# Touch_Menu_Board.net
KiCad netlist of a schematic drawn in EAGLE
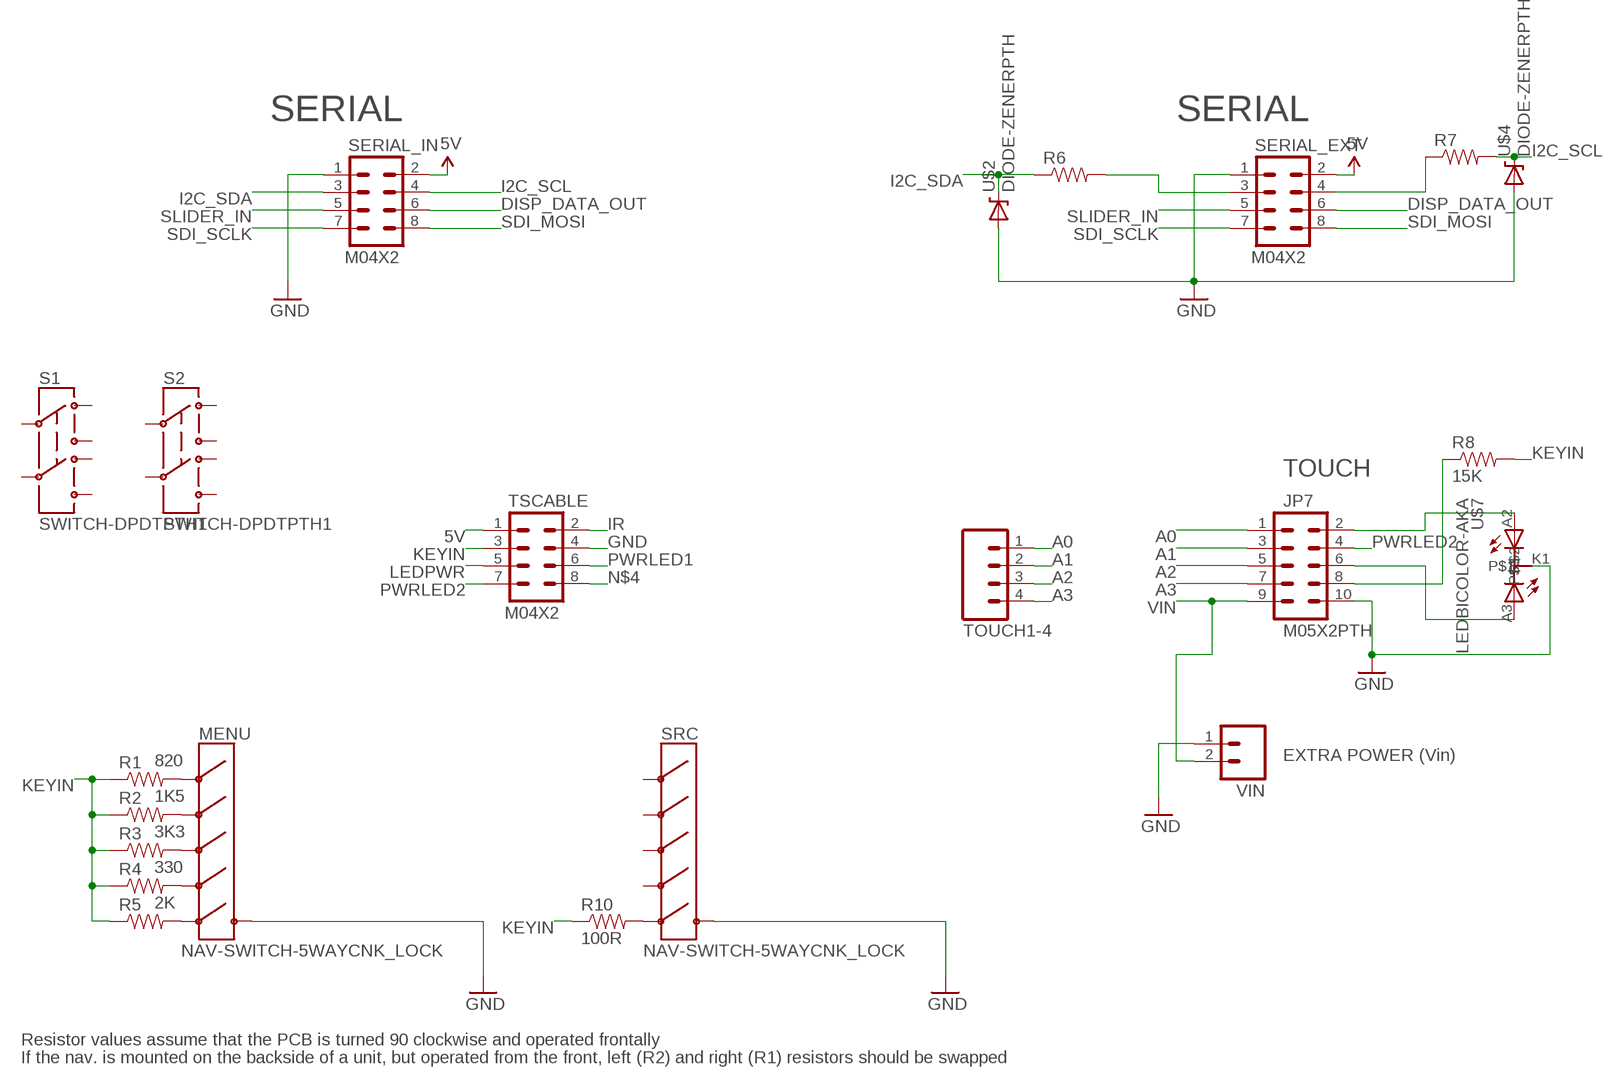
[diagram p0: schematic, sheet 1]

(export (version "E")
  (design (tool "Eeschema 10.0.6"))
  (components
    (comp (ref "JP7")
      (value "M05X2PTH")
      (footprint "eagle-import:AVR_ICSP")
      (libsource (lib "eagle-import") (part "M05X2PTH"))
    )
    (comp (ref "MENU")
      (value "NAV-SWITCH-5WAYCNK_LOCK")
      (footprint "eagle-import:NAV-SWITCH-5WAY")
      (libsource (lib "eagle-import") (part "NAV-SWITCH-5WAYCNK_LOCK"))
    )
    (comp (ref "R1")
      (value "820")
      (footprint "eagle-import:0603-RES")
      (libsource (lib "eagle-import") (part "RESISTOR0603-RES"))
    )
    (comp (ref "R2")
      (value "1K5")
      (footprint "eagle-import:0603-RES")
      (libsource (lib "eagle-import") (part "RESISTOR0603-RES"))
    )
    (comp (ref "R3")
      (value "3K3")
      (footprint "eagle-import:0603-RES")
      (libsource (lib "eagle-import") (part "RESISTOR0603-RES"))
    )
    (comp (ref "R4")
      (value "330")
      (footprint "eagle-import:0603-RES")
      (libsource (lib "eagle-import") (part "RESISTOR0603-RES"))
    )
    (comp (ref "R5")
      (value "2K")
      (footprint "eagle-import:0603-RES")
      (libsource (lib "eagle-import") (part "RESISTOR0603-RES"))
    )
    (comp (ref "R6")
      (value "RESISTORPTH-1/4W")
      (footprint "eagle-import:AXIAL-0.4")
      (libsource (lib "eagle-import") (part "RESISTORPTH-1/4W"))
    )
    (comp (ref "R7")
      (value "RESISTORPTH-1/4W")
      (footprint "eagle-import:AXIAL-0.4")
      (libsource (lib "eagle-import") (part "RESISTORPTH-1/4W"))
    )
    (comp (ref "R8")
      (value "15K")
      (footprint "eagle-import:0603-RES")
      (libsource (lib "eagle-import") (part "RESISTOR0603-RES"))
    )
    (comp (ref "R10")
      (value "100R")
      (footprint "eagle-import:0603-RES")
      (libsource (lib "eagle-import") (part "RESISTOR0603-RES"))
    )
    (comp (ref "S1")
      (value "SWITCH-DPDTPTH1")
      (footprint "eagle-import:TECONNECTIVITY-DPDT")
      (libsource (lib "eagle-import") (part "SWITCH-DPDTPTH1"))
    )
    (comp (ref "S2")
      (value "SWITCH-DPDTPTH1")
      (footprint "eagle-import:TECONNECTIVITY-DPDT")
      (libsource (lib "eagle-import") (part "SWITCH-DPDTPTH1"))
    )
    (comp (ref "SERIAL_EXT")
      (value "M04X2")
      (footprint "eagle-import:2X4")
      (libsource (lib "eagle-import") (part "M04X2"))
    )
    (comp (ref "SERIAL_IN")
      (value "M04X2")
      (footprint "eagle-import:2X4")
      (libsource (lib "eagle-import") (part "M04X2"))
    )
    (comp (ref "SRC")
      (value "NAV-SWITCH-5WAYCNK_LOCK")
      (footprint "eagle-import:NAV-SWITCH-5WAY")
      (libsource (lib "eagle-import") (part "NAV-SWITCH-5WAYCNK_LOCK"))
    )
    (comp (ref "TOUCH1-4")
      (value "M04PTH")
      (footprint "eagle-import:1X04")
      (libsource (lib "eagle-import") (part "M04PTH"))
    )
    (comp (ref "TSCABLE")
      (value "M04X2")
      (footprint "eagle-import:2X4")
      (libsource (lib "eagle-import") (part "M04X2"))
    )
    (comp (ref "U$2")
      (value "DIODE-ZENERPTH")
      (footprint "eagle-import:DIODE-ZENER")
      (libsource (lib "eagle-import") (part "DIODE-ZENERPTH"))
    )
    (comp (ref "U$4")
      (value "DIODE-ZENERPTH")
      (footprint "eagle-import:DIODE-ZENER")
      (libsource (lib "eagle-import") (part "DIODE-ZENERPTH"))
    )
    (comp (ref "U$7")
      (value "LEDBICOLOR-AKA")
      (footprint "eagle-import:LED5MM-BICOLOR")
      (libsource (lib "eagle-import") (part "LEDBICOLOR-AKA"))
    )
    (comp (ref "VIN")
      (value "M02PTH")
      (footprint "eagle-import:1X02")
      (libsource (lib "eagle-import") (part "M02PTH"))
    )
  )
  (nets
    (net (code "1") (name "/A0") (class "Default")
      (node (ref "JP7") (pin "1") (pinfunction "1_1") (pintype "passive"))
      (node (ref "TOUCH1-4") (pin "1") (pinfunction "1_1") (pintype "passive"))
    )
    (net (code "2") (name "/A1") (class "Default")
      (node (ref "JP7") (pin "3") (pinfunction "3_3") (pintype "passive"))
      (node (ref "TOUCH1-4") (pin "2") (pinfunction "2_2") (pintype "passive"))
    )
    (net (code "3") (name "/A2") (class "Default")
      (node (ref "JP7") (pin "5") (pinfunction "5_5") (pintype "passive"))
      (node (ref "TOUCH1-4") (pin "3") (pinfunction "3_3") (pintype "passive"))
    )
    (net (code "4") (name "/A3") (class "Default")
      (node (ref "JP7") (pin "7") (pinfunction "7_7") (pintype "passive"))
      (node (ref "TOUCH1-4") (pin "4") (pinfunction "4_4") (pintype "passive"))
    )
    (net (code "5") (name "/DISP_DATA_OUT") (class "Default")
      (node (ref "SERIAL_EXT") (pin "6") (pinfunction "6_6") (pintype "passive"))
      (node (ref "SERIAL_IN") (pin "6") (pinfunction "6_6") (pintype "passive"))
    )
    (net (code "6") (name "/I2C_SCL") (class "Default")
      (node (ref "R7") (pin "P$2") (pinfunction "2_P$2") (pintype "passive"))
      (node (ref "SERIAL_IN") (pin "4") (pinfunction "4_4") (pintype "passive"))
      (node (ref "U$4") (pin "P$1") (pinfunction "C_P$1") (pintype "passive"))
    )
    (net (code "7") (name "/I2C_SDA") (class "Default")
      (node (ref "R6") (pin "P$1") (pinfunction "1_P$1") (pintype "passive"))
      (node (ref "SERIAL_IN") (pin "3") (pinfunction "3_3") (pintype "passive"))
      (node (ref "U$2") (pin "P$1") (pinfunction "C_P$1") (pintype "passive"))
    )
    (net (code "8") (name "/IR") (class "Default")
      (node (ref "TSCABLE") (pin "2") (pinfunction "2_2") (pintype "passive"))
    )
    (net (code "9") (name "/KEYIN") (class "Default")
      (node (ref "R1") (pin "1") (pinfunction "1_1") (pintype "passive"))
      (node (ref "R10") (pin "1") (pinfunction "1_1") (pintype "passive"))
      (node (ref "R2") (pin "1") (pinfunction "1_1") (pintype "passive"))
      (node (ref "R3") (pin "1") (pinfunction "1_1") (pintype "passive"))
      (node (ref "R4") (pin "1") (pinfunction "1_1") (pintype "passive"))
      (node (ref "R5") (pin "1") (pinfunction "1_1") (pintype "passive"))
      (node (ref "R8") (pin "2") (pinfunction "2_2") (pintype "passive"))
      (node (ref "TSCABLE") (pin "3") (pinfunction "3_3") (pintype "passive"))
    )
    (net (code "10") (name "/LEDPWR") (class "Default")
      (node (ref "TSCABLE") (pin "5") (pinfunction "5_5") (pintype "passive"))
    )
    (net (code "11") (name "/N$4") (class "Default")
      (node (ref "TSCABLE") (pin "8") (pinfunction "8_8") (pintype "passive"))
    )
    (net (code "12") (name "/PWRLED1") (class "Default")
      (node (ref "TSCABLE") (pin "6") (pinfunction "6_6") (pintype "passive"))
    )
    (net (code "13") (name "/PWRLED2") (class "Default")
      (node (ref "JP7") (pin "4") (pinfunction "4_4") (pintype "passive"))
      (node (ref "TSCABLE") (pin "7") (pinfunction "7_7") (pintype "passive"))
    )
    (net (code "14") (name "/SDI_MOSI") (class "Default")
      (node (ref "SERIAL_EXT") (pin "8") (pinfunction "8_8") (pintype "passive"))
      (node (ref "SERIAL_IN") (pin "8") (pinfunction "8_8") (pintype "passive"))
    )
    (net (code "15") (name "/SDI_SCLK") (class "Default")
      (node (ref "SERIAL_EXT") (pin "7") (pinfunction "7_7") (pintype "passive"))
      (node (ref "SERIAL_IN") (pin "7") (pinfunction "7_7") (pintype "passive"))
    )
    (net (code "16") (name "/SLIDER_IN") (class "Default")
      (node (ref "SERIAL_EXT") (pin "5") (pinfunction "5_5") (pintype "passive"))
      (node (ref "SERIAL_IN") (pin "5") (pinfunction "5_5") (pintype "passive"))
    )
    (net (code "17") (name "/VIN") (class "Default")
      (node (ref "JP7") (pin "9") (pinfunction "9_9") (pintype "passive"))
      (node (ref "VIN") (pin "2") (pinfunction "2_2") (pintype "passive"))
    )
    (net (code "18") (name "5V") (class "Default")
      (node (ref "SERIAL_EXT") (pin "2") (pinfunction "2_2") (pintype "passive"))
      (node (ref "SERIAL_IN") (pin "2") (pinfunction "2_2") (pintype "passive"))
      (node (ref "TSCABLE") (pin "1") (pinfunction "1_1") (pintype "passive"))
    )
    (net (code "19") (name "GND") (class "Default")
      (node (ref "JP7") (pin "10") (pinfunction "10_10") (pintype "passive"))
      (node (ref "MENU") (pin "PIN4") (pinfunction "COMMON_PIN4") (pintype "bidirectional"))
      (node (ref "SERIAL_EXT") (pin "1") (pinfunction "1_1") (pintype "passive"))
      (node (ref "SERIAL_IN") (pin "1") (pinfunction "1_1") (pintype "passive"))
      (node (ref "SRC") (pin "PIN4") (pinfunction "COMMON_PIN4") (pintype "bidirectional"))
      (node (ref "TSCABLE") (pin "4") (pinfunction "4_4") (pintype "passive"))
      (node (ref "U$2") (pin "P$2") (pinfunction "A_P$2") (pintype "passive"))
      (node (ref "U$4") (pin "P$2") (pinfunction "A_P$2") (pintype "passive"))
      (node (ref "U$7") (pin "K1") (pinfunction "P$1_K1") (pintype "bidirectional"))
      (node (ref "VIN") (pin "1") (pinfunction "1_1") (pintype "passive"))
    )
    (net (code "20") (name "Net-(JP7-Pad8)") (class "Default")
      (node (ref "JP7") (pin "8") (pinfunction "8_8") (pintype "passive"))
      (node (ref "R8") (pin "1") (pinfunction "1_1") (pintype "passive"))
    )
    (net (code "21") (name "Net-(MENU-DWN)") (class "Default")
      (node (ref "MENU") (pin "PIN3") (pinfunction "DWN_PIN3") (pintype "bidirectional"))
      (node (ref "R2") (pin "2") (pinfunction "2_2") (pintype "passive"))
    )
    (net (code "22") (name "Net-(MENU-LEFT)") (class "Default")
      (node (ref "MENU") (pin "PIN2") (pinfunction "LEFT_PIN2") (pintype "bidirectional"))
      (node (ref "R3") (pin "2") (pinfunction "2_2") (pintype "passive"))
    )
    (net (code "23") (name "Net-(MENU-PUSH)") (class "Default")
      (node (ref "MENU") (pin "PIN6") (pinfunction "PUSH_PIN6") (pintype "bidirectional"))
      (node (ref "R5") (pin "2") (pinfunction "2_2") (pintype "passive"))
    )
    (net (code "24") (name "Net-(MENU-RIGHT)") (class "Default")
      (node (ref "MENU") (pin "PIN5") (pinfunction "RIGHT_PIN5") (pintype "bidirectional"))
      (node (ref "R4") (pin "2") (pinfunction "2_2") (pintype "passive"))
    )
    (net (code "25") (name "Net-(MENU-UP)") (class "Default")
      (node (ref "MENU") (pin "PIN1") (pinfunction "UP_PIN1") (pintype "bidirectional"))
      (node (ref "R1") (pin "2") (pinfunction "2_2") (pintype "passive"))
    )
    (net (code "26") (name "Net-(R6-2)") (class "Default")
      (node (ref "R6") (pin "P$2") (pinfunction "2_P$2") (pintype "passive"))
      (node (ref "SERIAL_EXT") (pin "3") (pinfunction "3_3") (pintype "passive"))
    )
    (net (code "27") (name "Net-(R7-1)") (class "Default")
      (node (ref "R7") (pin "P$1") (pinfunction "1_P$1") (pintype "passive"))
      (node (ref "SERIAL_EXT") (pin "4") (pinfunction "4_4") (pintype "passive"))
    )
    (net (code "28") (name "Net-(SRC-PUSH)") (class "Default")
      (node (ref "R10") (pin "2") (pinfunction "2_2") (pintype "passive"))
      (node (ref "SRC") (pin "PIN6") (pinfunction "PUSH_PIN6") (pintype "bidirectional"))
    )
    (net (code "29") (name "Net-(U$7-P$2)") (class "Default")
      (node (ref "JP7") (pin "2") (pinfunction "2_2") (pintype "passive"))
      (node (ref "U$7") (pin "A2") (pinfunction "P$2_A2") (pintype "bidirectional"))
    )
    (net (code "30") (name "Net-(U$7-P$3)") (class "Default")
      (node (ref "JP7") (pin "6") (pinfunction "6_6") (pintype "passive"))
      (node (ref "U$7") (pin "A3") (pinfunction "P$3_A3") (pintype "bidirectional"))
    )
    (net (code "31") (name "unconnected-(S1-1-PadP$1)") (class "Default")
      (node (ref "S1") (pin "P$1") (pinfunction "1_P$1") (pintype "bidirectional"))
    )
    (net (code "32") (name "unconnected-(S1-2-PadP$2)") (class "Default")
      (node (ref "S1") (pin "P$2") (pinfunction "2_P$2") (pintype "bidirectional"))
    )
    (net (code "33") (name "unconnected-(S1-3-PadP$3)") (class "Default")
      (node (ref "S1") (pin "P$3") (pinfunction "3_P$3") (pintype "bidirectional"))
    )
    (net (code "34") (name "unconnected-(S1-4-PadP$4)") (class "Default")
      (node (ref "S1") (pin "P$4") (pinfunction "4_P$4") (pintype "bidirectional"))
    )
    (net (code "35") (name "unconnected-(S1-5-PadP$5)") (class "Default")
      (node (ref "S1") (pin "P$5") (pinfunction "5_P$5") (pintype "bidirectional"))
    )
    (net (code "36") (name "unconnected-(S1-6-PadP$6)") (class "Default")
      (node (ref "S1") (pin "P$6") (pinfunction "6_P$6") (pintype "bidirectional"))
    )
    (net (code "37") (name "unconnected-(S2-1-PadP$1)") (class "Default")
      (node (ref "S2") (pin "P$1") (pinfunction "1_P$1") (pintype "bidirectional"))
    )
    (net (code "38") (name "unconnected-(S2-2-PadP$2)") (class "Default")
      (node (ref "S2") (pin "P$2") (pinfunction "2_P$2") (pintype "bidirectional"))
    )
    (net (code "39") (name "unconnected-(S2-3-PadP$3)") (class "Default")
      (node (ref "S2") (pin "P$3") (pinfunction "3_P$3") (pintype "bidirectional"))
    )
    (net (code "40") (name "unconnected-(S2-4-PadP$4)") (class "Default")
      (node (ref "S2") (pin "P$4") (pinfunction "4_P$4") (pintype "bidirectional"))
    )
    (net (code "41") (name "unconnected-(S2-5-PadP$5)") (class "Default")
      (node (ref "S2") (pin "P$5") (pinfunction "5_P$5") (pintype "bidirectional"))
    )
    (net (code "42") (name "unconnected-(S2-6-PadP$6)") (class "Default")
      (node (ref "S2") (pin "P$6") (pinfunction "6_P$6") (pintype "bidirectional"))
    )
    (net (code "43") (name "unconnected-(SRC-DWN-PadPIN3)") (class "Default")
      (node (ref "SRC") (pin "PIN3") (pinfunction "DWN_PIN3") (pintype "bidirectional"))
    )
    (net (code "44") (name "unconnected-(SRC-LEFT-PadPIN2)") (class "Default")
      (node (ref "SRC") (pin "PIN2") (pinfunction "LEFT_PIN2") (pintype "bidirectional"))
    )
    (net (code "45") (name "unconnected-(SRC-RIGHT-PadPIN5)") (class "Default")
      (node (ref "SRC") (pin "PIN5") (pinfunction "RIGHT_PIN5") (pintype "bidirectional"))
    )
    (net (code "46") (name "unconnected-(SRC-UP-PadPIN1)") (class "Default")
      (node (ref "SRC") (pin "PIN1") (pinfunction "UP_PIN1") (pintype "bidirectional"))
    )
  )
)
